# Sheet_2.net
KiCad netlist of a schematic drawn in Altium Designer
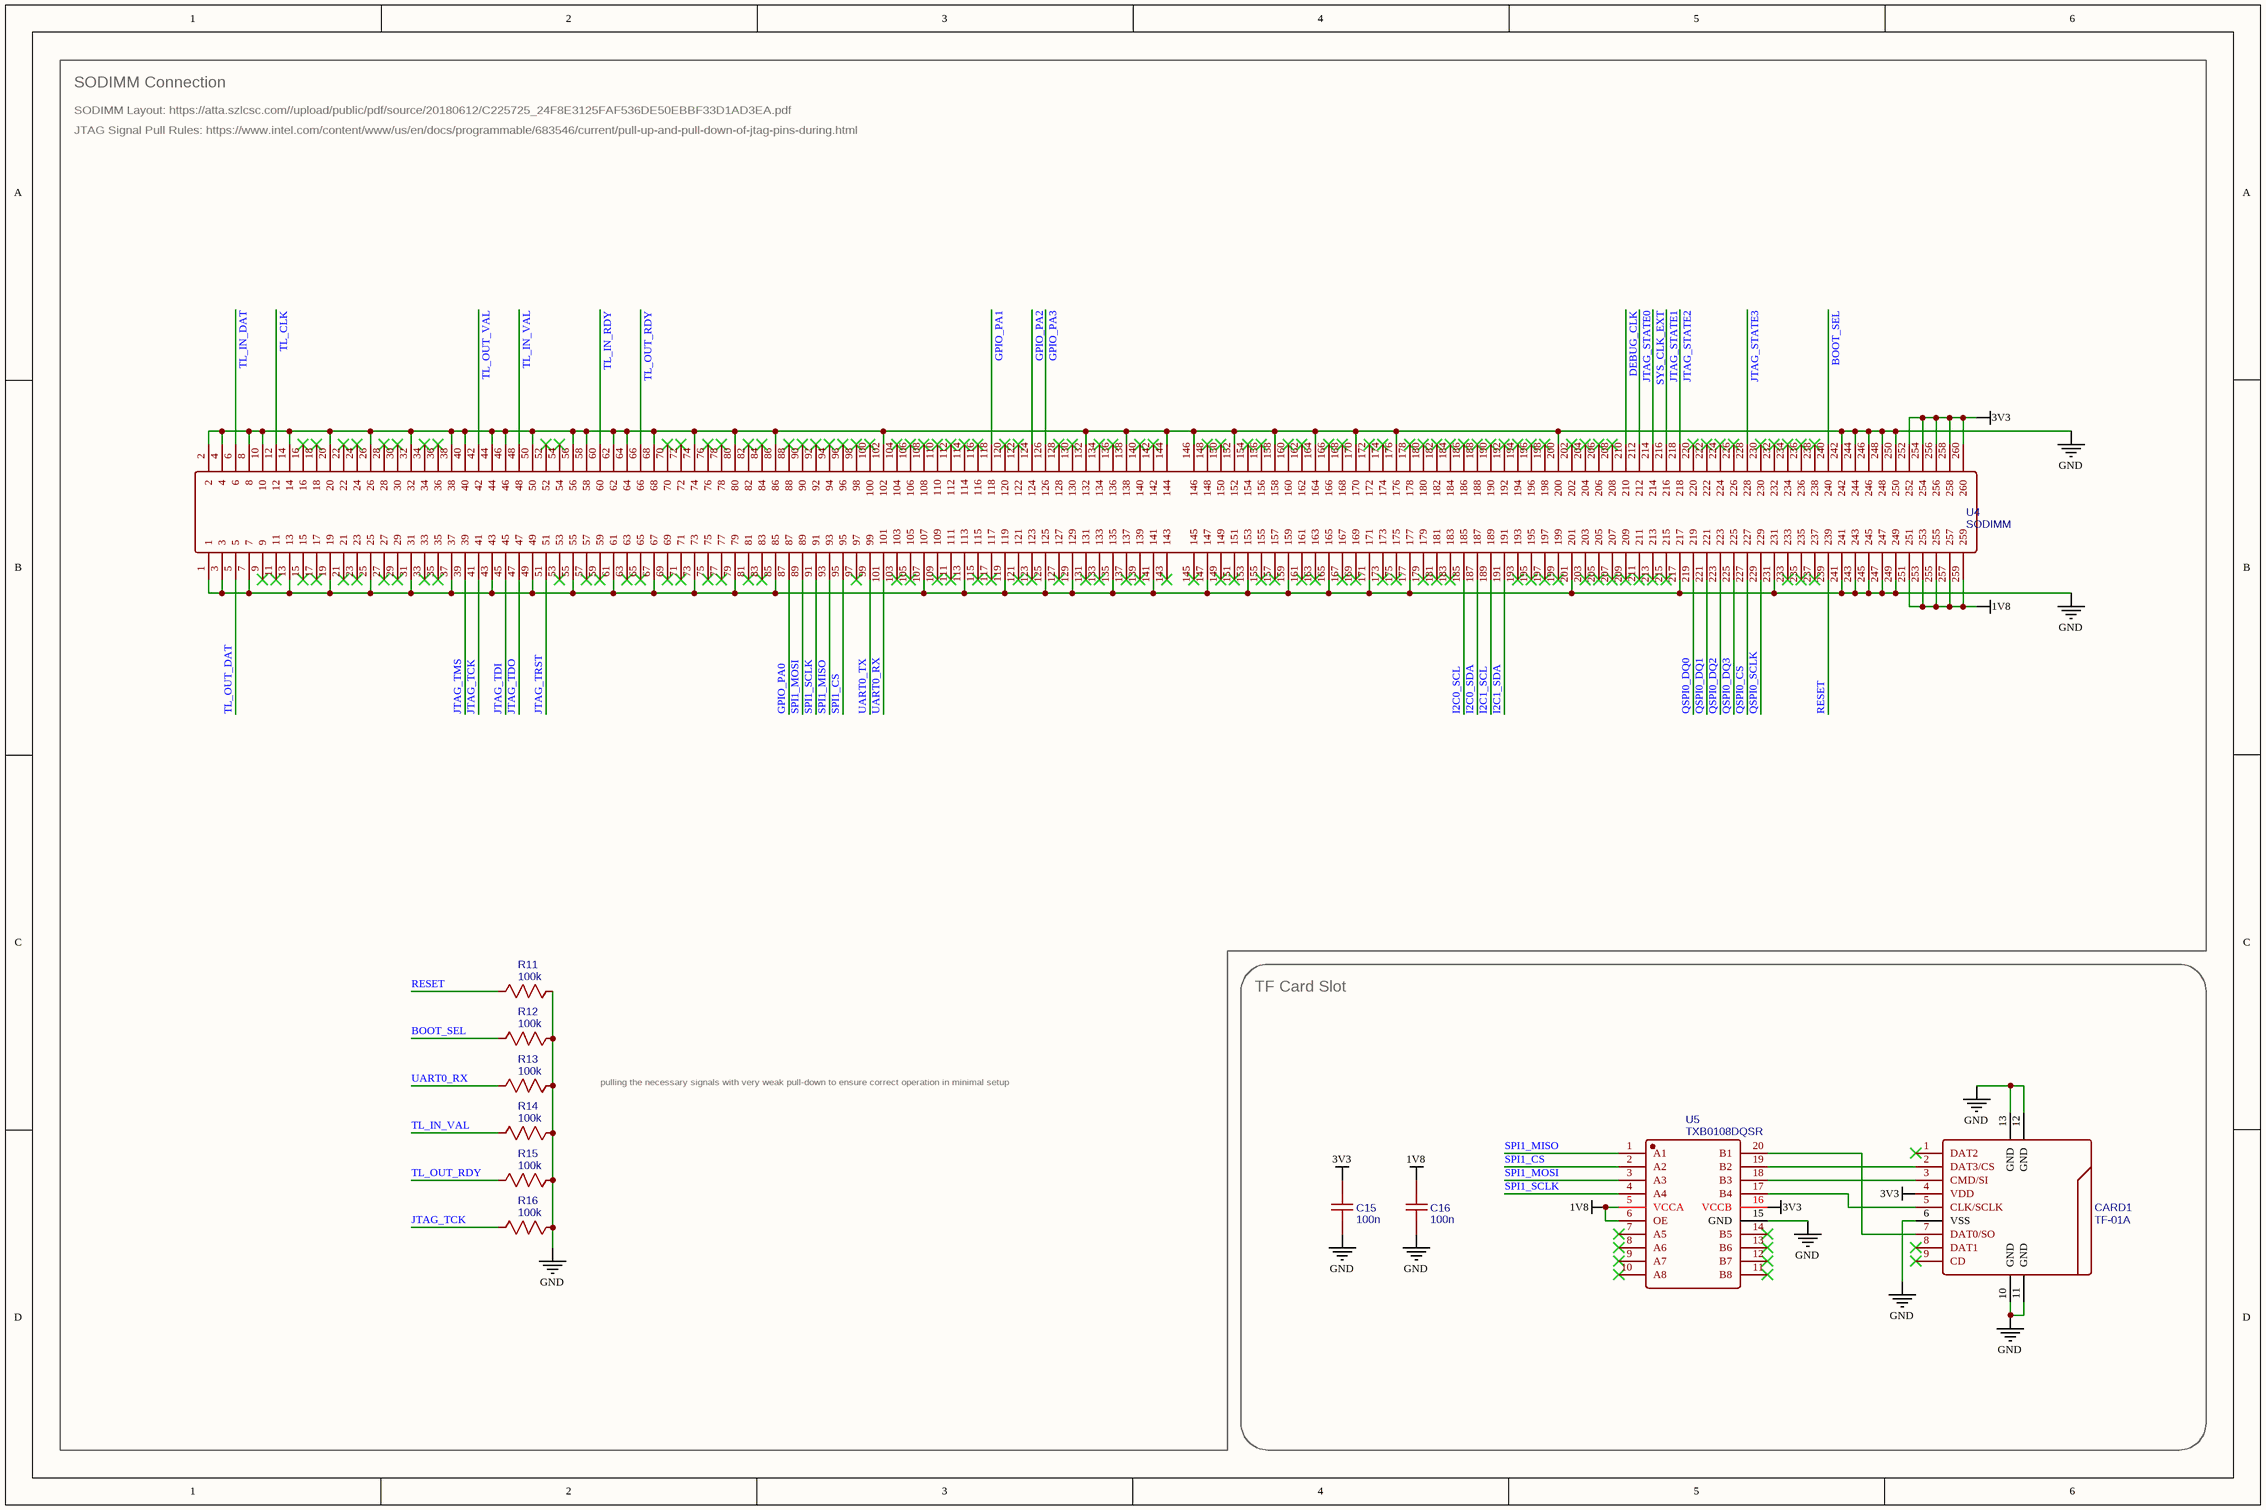
[diagram p0: Sheet_2.schdoc]

(export (version "E")
  (design (tool "Eeschema 10.0.6"))
  (components
    (comp (ref "C15")
      (value "100n")
      (footprint "CAPA-0402")
      (fields
        (field (name "BOM_SUPPLIER PART") "C307331")
        (field (name "BOM_MANUFACTURER PART") "CL05B104KB54PNC")
      )
      (libsource (lib "altium-import") (part "root_1_100n_"))
    )
    (comp (ref "C16")
      (value "100n")
      (footprint "CAPA-0402")
      (fields
        (field (name "BOM_SUPPLIER PART") "C307331")
        (field (name "BOM_MANUFACTURER PART") "CL05B104KB54PNC")
      )
      (libsource (lib "altium-import") (part "root_1_100n_"))
    )
    (comp (ref "CARD1")
      (value "TF-01A")
      (footprint "TF-SMD_TF-01A")
      (fields (field (name "BOM_SUPPLIER PART") "C91145"))
      (libsource (lib "altium-import") (part "root_0_TF-01A_"))
    )
    (comp (ref "R11")
      (value "100k")
      (footprint "RES-0402")
      (fields
        (field (name "BOM_SUPPLIER PART") "C25741")
        (field (name "BOM_MANUFACTURER PART") "0402WGF1003TCE")
      )
      (libsource (lib "altium-import") (part "root_0_100k_"))
    )
    (comp (ref "R12")
      (value "100k")
      (footprint "RES-0402")
      (fields
        (field (name "BOM_SUPPLIER PART") "C25741")
        (field (name "BOM_MANUFACTURER PART") "0402WGF1003TCE")
      )
      (libsource (lib "altium-import") (part "root_0_100k_"))
    )
    (comp (ref "R13")
      (value "100k")
      (footprint "RES-0402")
      (fields
        (field (name "BOM_SUPPLIER PART") "C25741")
        (field (name "BOM_MANUFACTURER PART") "0402WGF1003TCE")
      )
      (libsource (lib "altium-import") (part "root_0_100k_"))
    )
    (comp (ref "R14")
      (value "100k")
      (footprint "RES-0402")
      (fields
        (field (name "BOM_SUPPLIER PART") "C25741")
        (field (name "BOM_MANUFACTURER PART") "0402WGF1003TCE")
      )
      (libsource (lib "altium-import") (part "root_0_100k_"))
    )
    (comp (ref "R15")
      (value "100k")
      (footprint "RES-0402")
      (fields
        (field (name "BOM_SUPPLIER PART") "C25741")
        (field (name "BOM_MANUFACTURER PART") "0402WGF1003TCE")
      )
      (libsource (lib "altium-import") (part "root_0_100k_"))
    )
    (comp (ref "R16")
      (value "100k")
      (footprint "RES-0402")
      (fields
        (field (name "BOM_SUPPLIER PART") "C25741")
        (field (name "BOM_MANUFACTURER PART") "0402WGF1003TCE")
      )
      (libsource (lib "altium-import") (part "root_0_100k_"))
    )
    (comp (ref "U4")
      (value "SODIMM")
      (footprint "SODIMM 260")
      (fields (field (name "CONTRIBUTOR") "t-k-233"))
      (libsource (lib "altium-import") (part "root_0_SODIMM_"))
    )
    (comp (ref "U5")
      (value "TXB0108DQSR")
      (footprint "SON-20_L4.0-W2.0-P0.40-BL")
      (fields (field (name "BOM_SUPPLIER PART") "C427057"))
      (libsource (lib "altium-import") (part "root_0_TXB0108DQSR_"))
    )
  )
  (nets
    (net (code "1") (name "/BOOT_SEL") (class "Default")
      (node (ref "R12") (pin "1") (pinfunction "1_1") (pintype "passive"))
      (node (ref "U4") (pin "240") (pinfunction "240_240") (pintype "passive"))
    )
    (net (code "2") (name "/DEBUG_CLK") (class "Default")
      (node (ref "U4") (pin "210") (pinfunction "210_210") (pintype "passive"))
    )
    (net (code "3") (name "/GPIO_PA0") (class "Default")
      (node (ref "U4") (pin "87") (pinfunction "87_87") (pintype "passive"))
    )
    (net (code "4") (name "/GPIO_PA1") (class "Default")
      (node (ref "U4") (pin "118") (pinfunction "118_118") (pintype "passive"))
    )
    (net (code "5") (name "/GPIO_PA2") (class "Default")
      (node (ref "U4") (pin "124") (pinfunction "124_124") (pintype "passive"))
    )
    (net (code "6") (name "/GPIO_PA3") (class "Default")
      (node (ref "U4") (pin "126") (pinfunction "126_126") (pintype "passive"))
    )
    (net (code "7") (name "/I2C0_SCL") (class "Default")
      (node (ref "U4") (pin "185") (pinfunction "185_185") (pintype "passive"))
    )
    (net (code "8") (name "/I2C0_SDA") (class "Default")
      (node (ref "U4") (pin "187") (pinfunction "187_187") (pintype "passive"))
    )
    (net (code "9") (name "/I2C1_SCL") (class "Default")
      (node (ref "U4") (pin "189") (pinfunction "189_189") (pintype "passive"))
    )
    (net (code "10") (name "/I2C1_SDA") (class "Default")
      (node (ref "U4") (pin "191") (pinfunction "191_191") (pintype "passive"))
    )
    (net (code "11") (name "/JTAG_STATE0") (class "Default")
      (node (ref "U4") (pin "212") (pinfunction "212_212") (pintype "passive"))
    )
    (net (code "12") (name "/JTAG_STATE1") (class "Default")
      (node (ref "U4") (pin "216") (pinfunction "216_216") (pintype "passive"))
    )
    (net (code "13") (name "/JTAG_STATE2") (class "Default")
      (node (ref "U4") (pin "218") (pinfunction "218_218") (pintype "passive"))
    )
    (net (code "14") (name "/JTAG_STATE3") (class "Default")
      (node (ref "U4") (pin "228") (pinfunction "228_228") (pintype "passive"))
    )
    (net (code "15") (name "/JTAG_TCK") (class "Default")
      (node (ref "R16") (pin "1") (pinfunction "1_1") (pintype "passive"))
      (node (ref "U4") (pin "41") (pinfunction "41_41") (pintype "passive"))
    )
    (net (code "16") (name "/JTAG_TDI") (class "Default")
      (node (ref "U4") (pin "45") (pinfunction "45_45") (pintype "passive"))
    )
    (net (code "17") (name "/JTAG_TDO") (class "Default")
      (node (ref "U4") (pin "47") (pinfunction "47_47") (pintype "passive"))
    )
    (net (code "18") (name "/JTAG_TMS") (class "Default")
      (node (ref "U4") (pin "39") (pinfunction "39_39") (pintype "passive"))
    )
    (net (code "19") (name "/JTAG_TRST") (class "Default")
      (node (ref "U4") (pin "51") (pinfunction "51_51") (pintype "passive"))
    )
    (net (code "20") (name "/QSPI0_CS") (class "Default")
      (node (ref "U4") (pin "227") (pinfunction "227_227") (pintype "passive"))
    )
    (net (code "21") (name "/QSPI0_DQ0") (class "Default")
      (node (ref "U4") (pin "219") (pinfunction "219_219") (pintype "passive"))
    )
    (net (code "22") (name "/QSPI0_DQ1") (class "Default")
      (node (ref "U4") (pin "221") (pinfunction "221_221") (pintype "passive"))
    )
    (net (code "23") (name "/QSPI0_DQ2") (class "Default")
      (node (ref "U4") (pin "223") (pinfunction "223_223") (pintype "passive"))
    )
    (net (code "24") (name "/QSPI0_DQ3") (class "Default")
      (node (ref "U4") (pin "225") (pinfunction "225_225") (pintype "passive"))
    )
    (net (code "25") (name "/QSPI0_SCLK") (class "Default")
      (node (ref "U4") (pin "229") (pinfunction "229_229") (pintype "passive"))
    )
    (net (code "26") (name "/RESET") (class "Default")
      (node (ref "R11") (pin "1") (pinfunction "1_1") (pintype "passive"))
      (node (ref "U4") (pin "239") (pinfunction "239_239") (pintype "passive"))
    )
    (net (code "27") (name "/SPI1_CS") (class "Default")
      (node (ref "U4") (pin "95") (pinfunction "95_95") (pintype "passive"))
      (node (ref "U5") (pin "2") (pinfunction "A2_2") (pintype "passive"))
    )
    (net (code "28") (name "/SPI1_MISO") (class "Default")
      (node (ref "U4") (pin "93") (pinfunction "93_93") (pintype "passive"))
      (node (ref "U5") (pin "1") (pinfunction "A1_1") (pintype "passive"))
    )
    (net (code "29") (name "/SPI1_MOSI") (class "Default")
      (node (ref "U4") (pin "89") (pinfunction "89_89") (pintype "passive"))
      (node (ref "U5") (pin "3") (pinfunction "A3_3") (pintype "passive"))
    )
    (net (code "30") (name "/SPI1_SCLK") (class "Default")
      (node (ref "U4") (pin "91") (pinfunction "91_91") (pintype "passive"))
      (node (ref "U5") (pin "4") (pinfunction "A4_4") (pintype "passive"))
    )
    (net (code "31") (name "/SYS_CLK_EXT") (class "Default")
      (node (ref "U4") (pin "214") (pinfunction "214_214") (pintype "passive"))
    )
    (net (code "32") (name "/TL_CLK") (class "Default")
      (node (ref "U4") (pin "12") (pinfunction "12_12") (pintype "passive"))
    )
    (net (code "33") (name "/TL_IN_DAT") (class "Default")
      (node (ref "U4") (pin "6") (pinfunction "6_6") (pintype "passive"))
    )
    (net (code "34") (name "/TL_IN_RDY") (class "Default")
      (node (ref "U4") (pin "60") (pinfunction "60_60") (pintype "passive"))
    )
    (net (code "35") (name "/TL_IN_VAL") (class "Default")
      (node (ref "R14") (pin "1") (pinfunction "1_1") (pintype "passive"))
      (node (ref "U4") (pin "48") (pinfunction "48_48") (pintype "passive"))
    )
    (net (code "36") (name "/TL_OUT_DAT") (class "Default")
      (node (ref "U4") (pin "5") (pinfunction "5_5") (pintype "passive"))
    )
    (net (code "37") (name "/TL_OUT_RDY") (class "Default")
      (node (ref "R15") (pin "1") (pinfunction "1_1") (pintype "passive"))
      (node (ref "U4") (pin "66") (pinfunction "66_66") (pintype "passive"))
    )
    (net (code "38") (name "/TL_OUT_VAL") (class "Default")
      (node (ref "U4") (pin "42") (pinfunction "42_42") (pintype "passive"))
    )
    (net (code "39") (name "/UART0_RX") (class "Default")
      (node (ref "R13") (pin "1") (pinfunction "1_1") (pintype "passive"))
      (node (ref "U4") (pin "101") (pinfunction "101_101") (pintype "passive"))
    )
    (net (code "40") (name "/UART0_TX") (class "Default")
      (node (ref "U4") (pin "99") (pinfunction "99_99") (pintype "passive"))
    )
    (net (code "41") (name "1V8") (class "Default")
      (node (ref "C16") (pin "2") (pinfunction "2_2") (pintype "passive"))
      (node (ref "U4") (pin "251") (pinfunction "251_251") (pintype "passive"))
      (node (ref "U4") (pin "253") (pinfunction "253_253") (pintype "passive"))
      (node (ref "U4") (pin "255") (pinfunction "255_255") (pintype "passive"))
      (node (ref "U4") (pin "257") (pinfunction "257_257") (pintype "passive"))
      (node (ref "U4") (pin "259") (pinfunction "259_259") (pintype "passive"))
      (node (ref "U5") (pin "5") (pinfunction "VCCA_5") (pintype "passive"))
      (node (ref "U5") (pin "6") (pinfunction "OE_6") (pintype "passive"))
    )
    (net (code "42") (name "3V3") (class "Default")
      (node (ref "C15") (pin "2") (pinfunction "2_2") (pintype "passive"))
      (node (ref "CARD1") (pin "4") (pinfunction "VDD_4") (pintype "passive"))
      (node (ref "U4") (pin "252") (pinfunction "252_252") (pintype "passive"))
      (node (ref "U4") (pin "254") (pinfunction "254_254") (pintype "passive"))
      (node (ref "U4") (pin "256") (pinfunction "256_256") (pintype "passive"))
      (node (ref "U4") (pin "258") (pinfunction "258_258") (pintype "passive"))
      (node (ref "U4") (pin "260") (pinfunction "260_260") (pintype "passive"))
      (node (ref "U5") (pin "16") (pinfunction "VCCB_16") (pintype "passive"))
    )
    (net (code "43") (name "GND") (class "Default")
      (node (ref "C15") (pin "1") (pinfunction "1_1") (pintype "passive"))
      (node (ref "C16") (pin "1") (pinfunction "1_1") (pintype "passive"))
      (node (ref "CARD1") (pin "10") (pinfunction "GND_10") (pintype "passive"))
      (node (ref "CARD1") (pin "11") (pinfunction "GND_11") (pintype "passive"))
      (node (ref "CARD1") (pin "12") (pinfunction "GND_12") (pintype "passive"))
      (node (ref "CARD1") (pin "13") (pinfunction "GND_13") (pintype "passive"))
      (node (ref "CARD1") (pin "6") (pinfunction "VSS_6") (pintype "passive"))
      (node (ref "R11") (pin "2") (pinfunction "2_2") (pintype "passive"))
      (node (ref "R12") (pin "2") (pinfunction "2_2") (pintype "passive"))
      (node (ref "R13") (pin "2") (pinfunction "2_2") (pintype "passive"))
      (node (ref "R14") (pin "2") (pinfunction "2_2") (pintype "passive"))
      (node (ref "R15") (pin "2") (pinfunction "2_2") (pintype "passive"))
      (node (ref "R16") (pin "2") (pinfunction "2_2") (pintype "passive"))
      (node (ref "U4") (pin "1") (pinfunction "1_1") (pintype "passive"))
      (node (ref "U4") (pin "10") (pinfunction "10_10") (pintype "passive"))
      (node (ref "U4") (pin "102") (pinfunction "102_102") (pintype "passive"))
      (node (ref "U4") (pin "107") (pinfunction "107_107") (pintype "passive"))
      (node (ref "U4") (pin "113") (pinfunction "113_113") (pintype "passive"))
      (node (ref "U4") (pin "119") (pinfunction "119_119") (pintype "passive"))
      (node (ref "U4") (pin "125") (pinfunction "125_125") (pintype "passive"))
      (node (ref "U4") (pin "129") (pinfunction "129_129") (pintype "passive"))
      (node (ref "U4") (pin "13") (pinfunction "13_13") (pintype "passive"))
      (node (ref "U4") (pin "132") (pinfunction "132_132") (pintype "passive"))
      (node (ref "U4") (pin "135") (pinfunction "135_135") (pintype "passive"))
      (node (ref "U4") (pin "138") (pinfunction "138_138") (pintype "passive"))
      (node (ref "U4") (pin "14") (pinfunction "14_14") (pintype "passive"))
      (node (ref "U4") (pin "141") (pinfunction "141_141") (pintype "passive"))
      (node (ref "U4") (pin "144") (pinfunction "144_144") (pintype "passive"))
      (node (ref "U4") (pin "146") (pinfunction "146_146") (pintype "passive"))
      (node (ref "U4") (pin "147") (pinfunction "147_147") (pintype "passive"))
      (node (ref "U4") (pin "152") (pinfunction "152_152") (pintype "passive"))
      (node (ref "U4") (pin "153") (pinfunction "153_153") (pintype "passive"))
      (node (ref "U4") (pin "158") (pinfunction "158_158") (pintype "passive"))
      (node (ref "U4") (pin "159") (pinfunction "159_159") (pintype "passive"))
      (node (ref "U4") (pin "164") (pinfunction "164_164") (pintype "passive"))
      (node (ref "U4") (pin "165") (pinfunction "165_165") (pintype "passive"))
      (node (ref "U4") (pin "170") (pinfunction "170_170") (pintype "passive"))
      (node (ref "U4") (pin "171") (pinfunction "171_171") (pintype "passive"))
      (node (ref "U4") (pin "176") (pinfunction "176_176") (pintype "passive"))
      (node (ref "U4") (pin "177") (pinfunction "177_177") (pintype "passive"))
      (node (ref "U4") (pin "19") (pinfunction "19_19") (pintype "passive"))
      (node (ref "U4") (pin "2") (pinfunction "2_2") (pintype "passive"))
      (node (ref "U4") (pin "20") (pinfunction "20_20") (pintype "passive"))
      (node (ref "U4") (pin "200") (pinfunction "200_200") (pintype "passive"))
      (node (ref "U4") (pin "201") (pinfunction "201_201") (pintype "passive"))
      (node (ref "U4") (pin "217") (pinfunction "217_217") (pintype "passive"))
      (node (ref "U4") (pin "231") (pinfunction "231_231") (pintype "passive"))
      (node (ref "U4") (pin "241") (pinfunction "241_241") (pintype "passive"))
      (node (ref "U4") (pin "242") (pinfunction "242_242") (pintype "passive"))
      (node (ref "U4") (pin "243") (pinfunction "243_243") (pintype "passive"))
      (node (ref "U4") (pin "244") (pinfunction "244_244") (pintype "passive"))
      (node (ref "U4") (pin "245") (pinfunction "245_245") (pintype "passive"))
      (node (ref "U4") (pin "246") (pinfunction "246_246") (pintype "passive"))
      (node (ref "U4") (pin "247") (pinfunction "247_247") (pintype "passive"))
      (node (ref "U4") (pin "248") (pinfunction "248_248") (pintype "passive"))
      (node (ref "U4") (pin "249") (pinfunction "249_249") (pintype "passive"))
      (node (ref "U4") (pin "25") (pinfunction "25_25") (pintype "passive"))
      (node (ref "U4") (pin "250") (pinfunction "250_250") (pintype "passive"))
      (node (ref "U4") (pin "26") (pinfunction "26_26") (pintype "passive"))
      (node (ref "U4") (pin "3") (pinfunction "3_3") (pintype "passive"))
      (node (ref "U4") (pin "31") (pinfunction "31_31") (pintype "passive"))
      (node (ref "U4") (pin "32") (pinfunction "32_32") (pintype "passive"))
      (node (ref "U4") (pin "37") (pinfunction "37_37") (pintype "passive"))
      (node (ref "U4") (pin "38") (pinfunction "38_38") (pintype "passive"))
      (node (ref "U4") (pin "4") (pinfunction "4_4") (pintype "passive"))
      (node (ref "U4") (pin "40") (pinfunction "40_40") (pintype "passive"))
      (node (ref "U4") (pin "43") (pinfunction "43_43") (pintype "passive"))
      (node (ref "U4") (pin "44") (pinfunction "44_44") (pintype "passive"))
      (node (ref "U4") (pin "46") (pinfunction "46_46") (pintype "passive"))
      (node (ref "U4") (pin "49") (pinfunction "49_49") (pintype "passive"))
      (node (ref "U4") (pin "50") (pinfunction "50_50") (pintype "passive"))
      (node (ref "U4") (pin "55") (pinfunction "55_55") (pintype "passive"))
      (node (ref "U4") (pin "56") (pinfunction "56_56") (pintype "passive"))
      (node (ref "U4") (pin "58") (pinfunction "58_58") (pintype "passive"))
      (node (ref "U4") (pin "61") (pinfunction "61_61") (pintype "passive"))
      (node (ref "U4") (pin "62") (pinfunction "62_62") (pintype "passive"))
      (node (ref "U4") (pin "64") (pinfunction "64_64") (pintype "passive"))
      (node (ref "U4") (pin "67") (pinfunction "67_67") (pintype "passive"))
      (node (ref "U4") (pin "68") (pinfunction "68_68") (pintype "passive"))
      (node (ref "U4") (pin "7") (pinfunction "7_7") (pintype "passive"))
      (node (ref "U4") (pin "73") (pinfunction "73_73") (pintype "passive"))
      (node (ref "U4") (pin "74") (pinfunction "74_74") (pintype "passive"))
      (node (ref "U4") (pin "79") (pinfunction "79_79") (pintype "passive"))
      (node (ref "U4") (pin "8") (pinfunction "8_8") (pintype "passive"))
      (node (ref "U4") (pin "80") (pinfunction "80_80") (pintype "passive"))
      (node (ref "U4") (pin "85") (pinfunction "85_85") (pintype "passive"))
      (node (ref "U4") (pin "86") (pinfunction "86_86") (pintype "passive"))
      (node (ref "U5") (pin "15") (pinfunction "GND_15") (pintype "passive"))
    )
    (net (code "44") (name "Net-(CARD1-CLK{slash}SCLK)") (class "Default")
      (node (ref "CARD1") (pin "5") (pinfunction "CLK/SCLK_5") (pintype "passive"))
      (node (ref "U5") (pin "17") (pinfunction "B4_17") (pintype "passive"))
    )
    (net (code "45") (name "Net-(CARD1-CMD{slash}SI)") (class "Default")
      (node (ref "CARD1") (pin "3") (pinfunction "CMD/SI_3") (pintype "passive"))
      (node (ref "U5") (pin "18") (pinfunction "B3_18") (pintype "passive"))
    )
    (net (code "46") (name "Net-(CARD1-DAT0{slash}SO)") (class "Default")
      (node (ref "CARD1") (pin "7") (pinfunction "DAT0/SO_7") (pintype "passive"))
      (node (ref "U5") (pin "20") (pinfunction "B1_20") (pintype "passive"))
    )
    (net (code "47") (name "Net-(CARD1-DAT3{slash}CS)") (class "Default")
      (node (ref "CARD1") (pin "2") (pinfunction "DAT3/CS_2") (pintype "passive"))
      (node (ref "U5") (pin "19") (pinfunction "B2_19") (pintype "passive"))
    )
    (net (code "48") (name "unconnected-(CARD1-CD-Pad9)") (class "Default")
      (node (ref "CARD1") (pin "9") (pinfunction "CD_9") (pintype "passive+no_connect"))
    )
    (net (code "49") (name "unconnected-(CARD1-DAT1-Pad8)") (class "Default")
      (node (ref "CARD1") (pin "8") (pinfunction "DAT1_8") (pintype "passive+no_connect"))
    )
    (net (code "50") (name "unconnected-(CARD1-DAT2-Pad1)") (class "Default")
      (node (ref "CARD1") (pin "1") (pinfunction "DAT2_1") (pintype "passive+no_connect"))
    )
    (net (code "51") (name "unconnected-(U4-Pad9)") (class "Default")
      (node (ref "U4") (pin "9") (pinfunction "9_9") (pintype "passive+no_connect"))
    )
    (net (code "52") (name "unconnected-(U4-Pad11)") (class "Default")
      (node (ref "U4") (pin "11") (pinfunction "11_11") (pintype "passive+no_connect"))
    )
    (net (code "53") (name "unconnected-(U4-Pad15)") (class "Default")
      (node (ref "U4") (pin "15") (pinfunction "15_15") (pintype "passive+no_connect"))
    )
    (net (code "54") (name "unconnected-(U4-Pad16)") (class "Default")
      (node (ref "U4") (pin "16") (pinfunction "16_16") (pintype "passive+no_connect"))
    )
    (net (code "55") (name "unconnected-(U4-Pad17)") (class "Default")
      (node (ref "U4") (pin "17") (pinfunction "17_17") (pintype "passive+no_connect"))
    )
    (net (code "56") (name "unconnected-(U4-Pad18)") (class "Default")
      (node (ref "U4") (pin "18") (pinfunction "18_18") (pintype "passive+no_connect"))
    )
    (net (code "57") (name "unconnected-(U4-Pad21)") (class "Default")
      (node (ref "U4") (pin "21") (pinfunction "21_21") (pintype "passive+no_connect"))
    )
    (net (code "58") (name "unconnected-(U4-Pad22)") (class "Default")
      (node (ref "U4") (pin "22") (pinfunction "22_22") (pintype "passive+no_connect"))
    )
    (net (code "59") (name "unconnected-(U4-Pad23)") (class "Default")
      (node (ref "U4") (pin "23") (pinfunction "23_23") (pintype "passive+no_connect"))
    )
    (net (code "60") (name "unconnected-(U4-Pad24)") (class "Default")
      (node (ref "U4") (pin "24") (pinfunction "24_24") (pintype "passive+no_connect"))
    )
    (net (code "61") (name "unconnected-(U4-Pad27)") (class "Default")
      (node (ref "U4") (pin "27") (pinfunction "27_27") (pintype "passive+no_connect"))
    )
    (net (code "62") (name "unconnected-(U4-Pad28)") (class "Default")
      (node (ref "U4") (pin "28") (pinfunction "28_28") (pintype "passive+no_connect"))
    )
    (net (code "63") (name "unconnected-(U4-Pad29)") (class "Default")
      (node (ref "U4") (pin "29") (pinfunction "29_29") (pintype "passive+no_connect"))
    )
    (net (code "64") (name "unconnected-(U4-Pad30)") (class "Default")
      (node (ref "U4") (pin "30") (pinfunction "30_30") (pintype "passive+no_connect"))
    )
    (net (code "65") (name "unconnected-(U4-Pad33)") (class "Default")
      (node (ref "U4") (pin "33") (pinfunction "33_33") (pintype "passive+no_connect"))
    )
    (net (code "66") (name "unconnected-(U4-Pad34)") (class "Default")
      (node (ref "U4") (pin "34") (pinfunction "34_34") (pintype "passive+no_connect"))
    )
    (net (code "67") (name "unconnected-(U4-Pad35)") (class "Default")
      (node (ref "U4") (pin "35") (pinfunction "35_35") (pintype "passive+no_connect"))
    )
    (net (code "68") (name "unconnected-(U4-Pad36)") (class "Default")
      (node (ref "U4") (pin "36") (pinfunction "36_36") (pintype "passive+no_connect"))
    )
    (net (code "69") (name "unconnected-(U4-Pad52)") (class "Default")
      (node (ref "U4") (pin "52") (pinfunction "52_52") (pintype "passive+no_connect"))
    )
    (net (code "70") (name "unconnected-(U4-Pad53)") (class "Default")
      (node (ref "U4") (pin "53") (pinfunction "53_53") (pintype "passive+no_connect"))
    )
    (net (code "71") (name "unconnected-(U4-Pad54)") (class "Default")
      (node (ref "U4") (pin "54") (pinfunction "54_54") (pintype "passive+no_connect"))
    )
    (net (code "72") (name "unconnected-(U4-Pad57)") (class "Default")
      (node (ref "U4") (pin "57") (pinfunction "57_57") (pintype "passive+no_connect"))
    )
    (net (code "73") (name "unconnected-(U4-Pad59)") (class "Default")
      (node (ref "U4") (pin "59") (pinfunction "59_59") (pintype "passive+no_connect"))
    )
    (net (code "74") (name "unconnected-(U4-Pad63)") (class "Default")
      (node (ref "U4") (pin "63") (pinfunction "63_63") (pintype "passive+no_connect"))
    )
    (net (code "75") (name "unconnected-(U4-Pad65)") (class "Default")
      (node (ref "U4") (pin "65") (pinfunction "65_65") (pintype "passive+no_connect"))
    )
    (net (code "76") (name "unconnected-(U4-Pad69)") (class "Default")
      (node (ref "U4") (pin "69") (pinfunction "69_69") (pintype "passive+no_connect"))
    )
    (net (code "77") (name "unconnected-(U4-Pad70)") (class "Default")
      (node (ref "U4") (pin "70") (pinfunction "70_70") (pintype "passive+no_connect"))
    )
    (net (code "78") (name "unconnected-(U4-Pad71)") (class "Default")
      (node (ref "U4") (pin "71") (pinfunction "71_71") (pintype "passive+no_connect"))
    )
    (net (code "79") (name "unconnected-(U4-Pad72)") (class "Default")
      (node (ref "U4") (pin "72") (pinfunction "72_72") (pintype "passive+no_connect"))
    )
    (net (code "80") (name "unconnected-(U4-Pad75)") (class "Default")
      (node (ref "U4") (pin "75") (pinfunction "75_75") (pintype "passive+no_connect"))
    )
    (net (code "81") (name "unconnected-(U4-Pad76)") (class "Default")
      (node (ref "U4") (pin "76") (pinfunction "76_76") (pintype "passive+no_connect"))
    )
    (net (code "82") (name "unconnected-(U4-Pad77)") (class "Default")
      (node (ref "U4") (pin "77") (pinfunction "77_77") (pintype "passive+no_connect"))
    )
    (net (code "83") (name "unconnected-(U4-Pad78)") (class "Default")
      (node (ref "U4") (pin "78") (pinfunction "78_78") (pintype "passive+no_connect"))
    )
    (net (code "84") (name "unconnected-(U4-Pad81)") (class "Default")
      (node (ref "U4") (pin "81") (pinfunction "81_81") (pintype "passive+no_connect"))
    )
    (net (code "85") (name "unconnected-(U4-Pad82)") (class "Default")
      (node (ref "U4") (pin "82") (pinfunction "82_82") (pintype "passive+no_connect"))
    )
    (net (code "86") (name "unconnected-(U4-Pad83)") (class "Default")
      (node (ref "U4") (pin "83") (pinfunction "83_83") (pintype "passive+no_connect"))
    )
    (net (code "87") (name "unconnected-(U4-Pad84)") (class "Default")
      (node (ref "U4") (pin "84") (pinfunction "84_84") (pintype "passive+no_connect"))
    )
    (net (code "88") (name "unconnected-(U4-Pad88)") (class "Default")
      (node (ref "U4") (pin "88") (pinfunction "88_88") (pintype "passive+no_connect"))
    )
    (net (code "89") (name "unconnected-(U4-Pad90)") (class "Default")
      (node (ref "U4") (pin "90") (pinfunction "90_90") (pintype "passive+no_connect"))
    )
    (net (code "90") (name "unconnected-(U4-Pad92)") (class "Default")
      (node (ref "U4") (pin "92") (pinfunction "92_92") (pintype "passive+no_connect"))
    )
    (net (code "91") (name "unconnected-(U4-Pad94)") (class "Default")
      (node (ref "U4") (pin "94") (pinfunction "94_94") (pintype "passive+no_connect"))
    )
    (net (code "92") (name "unconnected-(U4-Pad96)") (class "Default")
      (node (ref "U4") (pin "96") (pinfunction "96_96") (pintype "passive+no_connect"))
    )
    (net (code "93") (name "unconnected-(U4-Pad97)") (class "Default")
      (node (ref "U4") (pin "97") (pinfunction "97_97") (pintype "passive+no_connect"))
    )
    (net (code "94") (name "unconnected-(U4-Pad98)") (class "Default")
      (node (ref "U4") (pin "98") (pinfunction "98_98") (pintype "passive+no_connect"))
    )
    (net (code "95") (name "unconnected-(U4-Pad100)") (class "Default")
      (node (ref "U4") (pin "100") (pinfunction "100_100") (pintype "passive+no_connect"))
    )
    (net (code "96") (name "unconnected-(U4-Pad103)") (class "Default")
      (node (ref "U4") (pin "103") (pinfunction "103_103") (pintype "passive+no_connect"))
    )
    (net (code "97") (name "unconnected-(U4-Pad104)") (class "Default")
      (node (ref "U4") (pin "104") (pinfunction "104_104") (pintype "passive+no_connect"))
    )
    (net (code "98") (name "unconnected-(U4-Pad105)") (class "Default")
      (node (ref "U4") (pin "105") (pinfunction "105_105") (pintype "passive+no_connect"))
    )
    (net (code "99") (name "unconnected-(U4-Pad106)") (class "Default")
      (node (ref "U4") (pin "106") (pinfunction "106_106") (pintype "passive+no_connect"))
    )
    (net (code "100") (name "unconnected-(U4-Pad108)") (class "Default")
      (node (ref "U4") (pin "108") (pinfunction "108_108") (pintype "passive+no_connect"))
    )
    (net (code "101") (name "unconnected-(U4-Pad109)") (class "Default")
      (node (ref "U4") (pin "109") (pinfunction "109_109") (pintype "passive+no_connect"))
    )
    (net (code "102") (name "unconnected-(U4-Pad110)") (class "Default")
      (node (ref "U4") (pin "110") (pinfunction "110_110") (pintype "passive+no_connect"))
    )
    (net (code "103") (name "unconnected-(U4-Pad111)") (class "Default")
      (node (ref "U4") (pin "111") (pinfunction "111_111") (pintype "passive+no_connect"))
    )
    (net (code "104") (name "unconnected-(U4-Pad112)") (class "Default")
      (node (ref "U4") (pin "112") (pinfunction "112_112") (pintype "passive+no_connect"))
    )
    (net (code "105") (name "unconnected-(U4-Pad114)") (class "Default")
      (node (ref "U4") (pin "114") (pinfunction "114_114") (pintype "passive+no_connect"))
    )
    (net (code "106") (name "unconnected-(U4-Pad115)") (class "Default")
      (node (ref "U4") (pin "115") (pinfunction "115_115") (pintype "passive+no_connect"))
    )
    (net (code "107") (name "unconnected-(U4-Pad116)") (class "Default")
      (node (ref "U4") (pin "116") (pinfunction "116_116") (pintype "passive+no_connect"))
    )
    (net (code "108") (name "unconnected-(U4-Pad117)") (class "Default")
      (node (ref "U4") (pin "117") (pinfunction "117_117") (pintype "passive+no_connect"))
    )
    (net (code "109") (name "unconnected-(U4-Pad120)") (class "Default")
      (node (ref "U4") (pin "120") (pinfunction "120_120") (pintype "passive+no_connect"))
    )
    (net (code "110") (name "unconnected-(U4-Pad121)") (class "Default")
      (node (ref "U4") (pin "121") (pinfunction "121_121") (pintype "passive+no_connect"))
    )
    (net (code "111") (name "unconnected-(U4-Pad122)") (class "Default")
      (node (ref "U4") (pin "122") (pinfunction "122_122") (pintype "passive+no_connect"))
    )
    (net (code "112") (name "unconnected-(U4-Pad123)") (class "Default")
      (node (ref "U4") (pin "123") (pinfunction "123_123") (pintype "passive+no_connect"))
    )
    (net (code "113") (name "unconnected-(U4-Pad127)") (class "Default")
      (node (ref "U4") (pin "127") (pinfunction "127_127") (pintype "passive+no_connect"))
    )
    (net (code "114") (name "unconnected-(U4-Pad128)") (class "Default")
      (node (ref "U4") (pin "128") (pinfunction "128_128") (pintype "passive+no_connect"))
    )
    (net (code "115") (name "unconnected-(U4-Pad130)") (class "Default")
      (node (ref "U4") (pin "130") (pinfunction "130_130") (pintype "passive+no_connect"))
    )
    (net (code "116") (name "unconnected-(U4-Pad131)") (class "Default")
      (node (ref "U4") (pin "131") (pinfunction "131_131") (pintype "passive+no_connect"))
    )
    (net (code "117") (name "unconnected-(U4-Pad133)") (class "Default")
      (node (ref "U4") (pin "133") (pinfunction "133_133") (pintype "passive+no_connect"))
    )
    (net (code "118") (name "unconnected-(U4-Pad134)") (class "Default")
      (node (ref "U4") (pin "134") (pinfunction "134_134") (pintype "passive+no_connect"))
    )
    (net (code "119") (name "unconnected-(U4-Pad136)") (class "Default")
      (node (ref "U4") (pin "136") (pinfunction "136_136") (pintype "passive+no_connect"))
    )
    (net (code "120") (name "unconnected-(U4-Pad137)") (class "Default")
      (node (ref "U4") (pin "137") (pinfunction "137_137") (pintype "passive+no_connect"))
    )
    (net (code "121") (name "unconnected-(U4-Pad139)") (class "Default")
      (node (ref "U4") (pin "139") (pinfunction "139_139") (pintype "passive+no_connect"))
    )
    (net (code "122") (name "unconnected-(U4-Pad140)") (class "Default")
      (node (ref "U4") (pin "140") (pinfunction "140_140") (pintype "passive+no_connect"))
    )
    (net (code "123") (name "unconnected-(U4-Pad142)") (class "Default")
      (node (ref "U4") (pin "142") (pinfunction "142_142") (pintype "passive+no_connect"))
    )
    (net (code "124") (name "unconnected-(U4-Pad143)") (class "Default")
      (node (ref "U4") (pin "143") (pinfunction "143_143") (pintype "passive+no_connect"))
    )
    (net (code "125") (name "unconnected-(U4-Pad145)") (class "Default")
      (node (ref "U4") (pin "145") (pinfunction "145_145") (pintype "passive+no_connect"))
    )
    (net (code "126") (name "unconnected-(U4-Pad148)") (class "Default")
      (node (ref "U4") (pin "148") (pinfunction "148_148") (pintype "passive+no_connect"))
    )
    (net (code "127") (name "unconnected-(U4-Pad149)") (class "Default")
      (node (ref "U4") (pin "149") (pinfunction "149_149") (pintype "passive+no_connect"))
    )
    (net (code "128") (name "unconnected-(U4-Pad150)") (class "Default")
      (node (ref "U4") (pin "150") (pinfunction "150_150") (pintype "passive+no_connect"))
    )
    (net (code "129") (name "unconnected-(U4-Pad151)") (class "Default")
      (node (ref "U4") (pin "151") (pinfunction "151_151") (pintype "passive+no_connect"))
    )
    (net (code "130") (name "unconnected-(U4-Pad154)") (class "Default")
      (node (ref "U4") (pin "154") (pinfunction "154_154") (pintype "passive+no_connect"))
    )
    (net (code "131") (name "unconnected-(U4-Pad155)") (class "Default")
      (node (ref "U4") (pin "155") (pinfunction "155_155") (pintype "passive+no_connect"))
    )
    (net (code "132") (name "unconnected-(U4-Pad156)") (class "Default")
      (node (ref "U4") (pin "156") (pinfunction "156_156") (pintype "passive+no_connect"))
    )
    (net (code "133") (name "unconnected-(U4-Pad157)") (class "Default")
      (node (ref "U4") (pin "157") (pinfunction "157_157") (pintype "passive+no_connect"))
    )
    (net (code "134") (name "unconnected-(U4-Pad160)") (class "Default")
      (node (ref "U4") (pin "160") (pinfunction "160_160") (pintype "passive+no_connect"))
    )
    (net (code "135") (name "unconnected-(U4-Pad161)") (class "Default")
      (node (ref "U4") (pin "161") (pinfunction "161_161") (pintype "passive+no_connect"))
    )
    (net (code "136") (name "unconnected-(U4-Pad162)") (class "Default")
      (node (ref "U4") (pin "162") (pinfunction "162_162") (pintype "passive+no_connect"))
    )
    (net (code "137") (name "unconnected-(U4-Pad163)") (class "Default")
      (node (ref "U4") (pin "163") (pinfunction "163_163") (pintype "passive+no_connect"))
    )
    (net (code "138") (name "unconnected-(U4-Pad166)") (class "Default")
      (node (ref "U4") (pin "166") (pinfunction "166_166") (pintype "passive+no_connect"))
    )
    (net (code "139") (name "unconnected-(U4-Pad167)") (class "Default")
      (node (ref "U4") (pin "167") (pinfunction "167_167") (pintype "passive+no_connect"))
    )
    (net (code "140") (name "unconnected-(U4-Pad168)") (class "Default")
      (node (ref "U4") (pin "168") (pinfunction "168_168") (pintype "passive+no_connect"))
    )
    (net (code "141") (name "unconnected-(U4-Pad169)") (class "Default")
      (node (ref "U4") (pin "169") (pinfunction "169_169") (pintype "passive+no_connect"))
    )
    (net (code "142") (name "unconnected-(U4-Pad172)") (class "Default")
      (node (ref "U4") (pin "172") (pinfunction "172_172") (pintype "passive+no_connect"))
    )
    (net (code "143") (name "unconnected-(U4-Pad173)") (class "Default")
      (node (ref "U4") (pin "173") (pinfunction "173_173") (pintype "passive+no_connect"))
    )
    (net (code "144") (name "unconnected-(U4-Pad174)") (class "Default")
      (node (ref "U4") (pin "174") (pinfunction "174_174") (pintype "passive+no_connect"))
    )
    (net (code "145") (name "unconnected-(U4-Pad175)") (class "Default")
      (node (ref "U4") (pin "175") (pinfunction "175_175") (pintype "passive+no_connect"))
    )
    (net (code "146") (name "unconnected-(U4-Pad178)") (class "Default")
      (node (ref "U4") (pin "178") (pinfunction "178_178") (pintype "passive+no_connect"))
    )
    (net (code "147") (name "unconnected-(U4-Pad179)") (class "Default")
      (node (ref "U4") (pin "179") (pinfunction "179_179") (pintype "passive+no_connect"))
    )
    (net (code "148") (name "unconnected-(U4-Pad180)") (class "Default")
      (node (ref "U4") (pin "180") (pinfunction "180_180") (pintype "passive+no_connect"))
    )
    (net (code "149") (name "unconnected-(U4-Pad181)") (class "Default")
      (node (ref "U4") (pin "181") (pinfunction "181_181") (pintype "passive+no_connect"))
    )
    (net (code "150") (name "unconnected-(U4-Pad182)") (class "Default")
      (node (ref "U4") (pin "182") (pinfunction "182_182") (pintype "passive+no_connect"))
    )
    (net (code "151") (name "unconnected-(U4-Pad183)") (class "Default")
      (node (ref "U4") (pin "183") (pinfunction "183_183") (pintype "passive+no_connect"))
    )
    (net (code "152") (name "unconnected-(U4-Pad184)") (class "Default")
      (node (ref "U4") (pin "184") (pinfunction "184_184") (pintype "passive+no_connect"))
    )
    (net (code "153") (name "unconnected-(U4-Pad186)") (class "Default")
      (node (ref "U4") (pin "186") (pinfunction "186_186") (pintype "passive+no_connect"))
    )
    (net (code "154") (name "unconnected-(U4-Pad188)") (class "Default")
      (node (ref "U4") (pin "188") (pinfunction "188_188") (pintype "passive+no_connect"))
    )
    (net (code "155") (name "unconnected-(U4-Pad190)") (class "Default")
      (node (ref "U4") (pin "190") (pinfunction "190_190") (pintype "passive+no_connect"))
    )
    (net (code "156") (name "unconnected-(U4-Pad192)") (class "Default")
      (node (ref "U4") (pin "192") (pinfunction "192_192") (pintype "passive+no_connect"))
    )
    (net (code "157") (name "unconnected-(U4-Pad193)") (class "Default")
      (node (ref "U4") (pin "193") (pinfunction "193_193") (pintype "passive+no_connect"))
    )
    (net (code "158") (name "unconnected-(U4-Pad194)") (class "Default")
      (node (ref "U4") (pin "194") (pinfunction "194_194") (pintype "passive+no_connect"))
    )
    (net (code "159") (name "unconnected-(U4-Pad195)") (class "Default")
      (node (ref "U4") (pin "195") (pinfunction "195_195") (pintype "passive+no_connect"))
    )
    (net (code "160") (name "unconnected-(U4-Pad196)") (class "Default")
      (node (ref "U4") (pin "196") (pinfunction "196_196") (pintype "passive+no_connect"))
    )
    (net (code "161") (name "unconnected-(U4-Pad197)") (class "Default")
      (node (ref "U4") (pin "197") (pinfunction "197_197") (pintype "passive+no_connect"))
    )
    (net (code "162") (name "unconnected-(U4-Pad198)") (class "Default")
      (node (ref "U4") (pin "198") (pinfunction "198_198") (pintype "passive+no_connect"))
    )
    (net (code "163") (name "unconnected-(U4-Pad199)") (class "Default")
      (node (ref "U4") (pin "199") (pinfunction "199_199") (pintype "passive+no_connect"))
    )
    (net (code "164") (name "unconnected-(U4-Pad202)") (class "Default")
      (node (ref "U4") (pin "202") (pinfunction "202_202") (pintype "passive+no_connect"))
    )
    (net (code "165") (name "unconnected-(U4-Pad203)") (class "Default")
      (node (ref "U4") (pin "203") (pinfunction "203_203") (pintype "passive+no_connect"))
    )
    (net (code "166") (name "unconnected-(U4-Pad204)") (class "Default")
      (node (ref "U4") (pin "204") (pinfunction "204_204") (pintype "passive+no_connect"))
    )
    (net (code "167") (name "unconnected-(U4-Pad205)") (class "Default")
      (node (ref "U4") (pin "205") (pinfunction "205_205") (pintype "passive+no_connect"))
    )
    (net (code "168") (name "unconnected-(U4-Pad206)") (class "Default")
      (node (ref "U4") (pin "206") (pinfunction "206_206") (pintype "passive+no_connect"))
    )
    (net (code "169") (name "unconnected-(U4-Pad207)") (class "Default")
      (node (ref "U4") (pin "207") (pinfunction "207_207") (pintype "passive+no_connect"))
    )
    (net (code "170") (name "unconnected-(U4-Pad208)") (class "Default")
      (node (ref "U4") (pin "208") (pinfunction "208_208") (pintype "passive+no_connect"))
    )
    (net (code "171") (name "unconnected-(U4-Pad209)") (class "Default")
      (node (ref "U4") (pin "209") (pinfunction "209_209") (pintype "passive+no_connect"))
    )
    (net (code "172") (name "unconnected-(U4-Pad211)") (class "Default")
      (node (ref "U4") (pin "211") (pinfunction "211_211") (pintype "passive+no_connect"))
    )
    (net (code "173") (name "unconnected-(U4-Pad213)") (class "Default")
      (node (ref "U4") (pin "213") (pinfunction "213_213") (pintype "passive+no_connect"))
    )
    (net (code "174") (name "unconnected-(U4-Pad215)") (class "Default")
      (node (ref "U4") (pin "215") (pinfunction "215_215") (pintype "passive+no_connect"))
    )
    (net (code "175") (name "unconnected-(U4-Pad220)") (class "Default")
      (node (ref "U4") (pin "220") (pinfunction "220_220") (pintype "passive+no_connect"))
    )
    (net (code "176") (name "unconnected-(U4-Pad222)") (class "Default")
      (node (ref "U4") (pin "222") (pinfunction "222_222") (pintype "passive+no_connect"))
    )
    (net (code "177") (name "unconnected-(U4-Pad224)") (class "Default")
      (node (ref "U4") (pin "224") (pinfunction "224_224") (pintype "passive+no_connect"))
    )
    (net (code "178") (name "unconnected-(U4-Pad226)") (class "Default")
      (node (ref "U4") (pin "226") (pinfunction "226_226") (pintype "passive+no_connect"))
    )
    (net (code "179") (name "unconnected-(U4-Pad230)") (class "Default")
      (node (ref "U4") (pin "230") (pinfunction "230_230") (pintype "passive+no_connect"))
    )
    (net (code "180") (name "unconnected-(U4-Pad232)") (class "Default")
      (node (ref "U4") (pin "232") (pinfunction "232_232") (pintype "passive+no_connect"))
    )
    (net (code "181") (name "unconnected-(U4-Pad233)") (class "Default")
      (node (ref "U4") (pin "233") (pinfunction "233_233") (pintype "passive+no_connect"))
    )
    (net (code "182") (name "unconnected-(U4-Pad234)") (class "Default")
      (node (ref "U4") (pin "234") (pinfunction "234_234") (pintype "passive+no_connect"))
    )
    (net (code "183") (name "unconnected-(U4-Pad235)") (class "Default")
      (node (ref "U4") (pin "235") (pinfunction "235_235") (pintype "passive+no_connect"))
    )
    (net (code "184") (name "unconnected-(U4-Pad236)") (class "Default")
      (node (ref "U4") (pin "236") (pinfunction "236_236") (pintype "passive+no_connect"))
    )
    (net (code "185") (name "unconnected-(U4-Pad237)") (class "Default")
      (node (ref "U4") (pin "237") (pinfunction "237_237") (pintype "passive+no_connect"))
    )
    (net (code "186") (name "unconnected-(U4-Pad238)") (class "Default")
      (node (ref "U4") (pin "238") (pinfunction "238_238") (pintype "passive+no_connect"))
    )
    (net (code "187") (name "unconnected-(U5-A5-Pad7)") (class "Default")
      (node (ref "U5") (pin "7") (pinfunction "A5_7") (pintype "passive+no_connect"))
    )
    (net (code "188") (name "unconnected-(U5-A6-Pad8)") (class "Default")
      (node (ref "U5") (pin "8") (pinfunction "A6_8") (pintype "passive+no_connect"))
    )
    (net (code "189") (name "unconnected-(U5-A7-Pad9)") (class "Default")
      (node (ref "U5") (pin "9") (pinfunction "A7_9") (pintype "passive+no_connect"))
    )
    (net (code "190") (name "unconnected-(U5-A8-Pad10)") (class "Default")
      (node (ref "U5") (pin "10") (pinfunction "A8_10") (pintype "passive+no_connect"))
    )
    (net (code "191") (name "unconnected-(U5-B5-Pad14)") (class "Default")
      (node (ref "U5") (pin "14") (pinfunction "B5_14") (pintype "passive+no_connect"))
    )
    (net (code "192") (name "unconnected-(U5-B6-Pad13)") (class "Default")
      (node (ref "U5") (pin "13") (pinfunction "B6_13") (pintype "passive+no_connect"))
    )
    (net (code "193") (name "unconnected-(U5-B7-Pad12)") (class "Default")
      (node (ref "U5") (pin "12") (pinfunction "B7_12") (pintype "passive+no_connect"))
    )
    (net (code "194") (name "unconnected-(U5-B8-Pad11)") (class "Default")
      (node (ref "U5") (pin "11") (pinfunction "B8_11") (pintype "passive+no_connect"))
    )
  )
)
